# osi-brain_rev_1.net
KiCad netlist of a schematic drawn in EAGLE
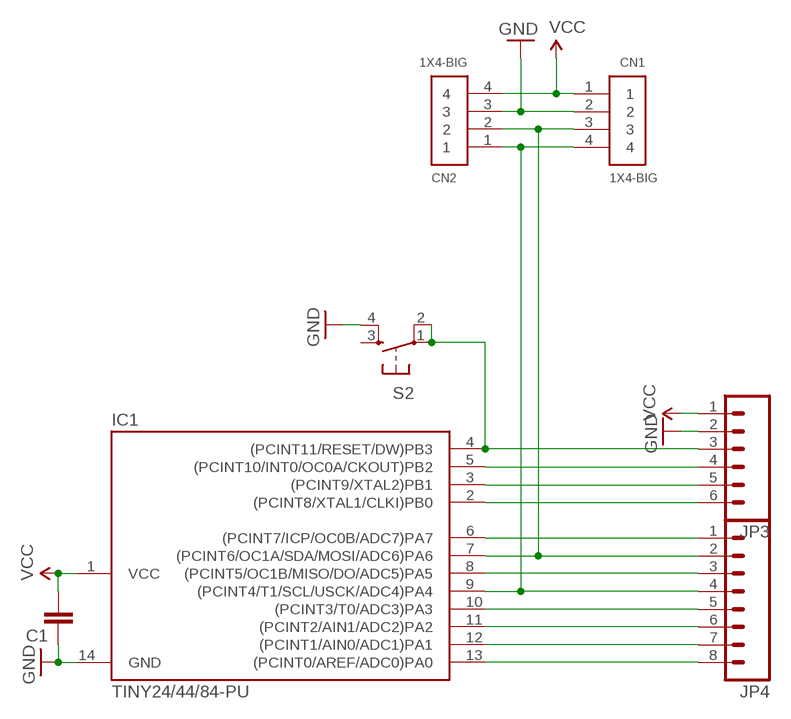
[diagram p0: schematic, sheet 1]

(export (version "E")
  (design (tool "Eeschema 10.0.6"))
  (components
    (comp (ref "C1")
      (value "CAPKIT")
      (footprint "eagle-import:CAP-PTH-SMALL-KIT")
      (libsource (lib "eagle-import") (part "CAPKIT"))
    )
    (comp (ref "CN1")
      (value "1X4-BIG")
      (footprint "eagle-import:1X04-BIG")
      (libsource (lib "eagle-import") (part "1X4-BIG"))
    )
    (comp (ref "CN2")
      (value "1X4-BIG")
      (footprint "eagle-import:1X04-BIG")
      (libsource (lib "eagle-import") (part "1X4-BIG"))
    )
    (comp (ref "IC1")
      (value "TINY24/44/84-PU")
      (footprint "eagle-import:DIL14")
      (libsource (lib "eagle-import") (part "TINY24/44/84-PU"))
    )
    (comp (ref "JP3")
      (value "M06SIP")
      (footprint "eagle-import:1X06")
      (libsource (lib "eagle-import") (part "M06SIP"))
    )
    (comp (ref "JP4")
      (value "M081X08")
      (footprint "eagle-import:1X08")
      (libsource (lib "eagle-import") (part "M081X08"))
    )
    (comp (ref "S2")
      (value "TAC_SWITCHPTH")
      (footprint "eagle-import:TACTILE-PTH")
      (libsource (lib "eagle-import") (part "TAC_SWITCHPTH"))
    )
  )
  (nets
    (net (code "1") (name "GND") (class "Default")
      (node (ref "C1") (pin "1") (pinfunction "1_1") (pintype "passive"))
      (node (ref "CN1") (pin "2") (pinfunction "2_2") (pintype "bidirectional"))
      (node (ref "CN2") (pin "3") (pinfunction "3_3") (pintype "bidirectional"))
      (node (ref "IC1") (pin "14") (pinfunction "GND_14") (pintype "power_in"))
      (node (ref "JP3") (pin "2") (pinfunction "2_2") (pintype "passive"))
      (node (ref "S2") (pin "4") (pinfunction "4_4") (pintype "passive"))
    )
    (net (code "2") (name "Net-(IC1-(PCINT0{slash}AREF{slash}ADC0)PA0)") (class "Default")
      (node (ref "IC1") (pin "13") (pinfunction "(PCINT0/AREF/ADC0)PA0_13") (pintype "bidirectional"))
      (node (ref "JP4") (pin "8") (pinfunction "8_8") (pintype "passive"))
    )
    (net (code "3") (name "Net-(IC1-(PCINT1{slash}AIN0{slash}ADC1)PA1)") (class "Default")
      (node (ref "IC1") (pin "12") (pinfunction "(PCINT1/AIN0/ADC1)PA1_12") (pintype "bidirectional"))
      (node (ref "JP4") (pin "7") (pinfunction "7_7") (pintype "passive"))
    )
    (net (code "4") (name "Net-(IC1-(PCINT2{slash}AIN1{slash}ADC2)PA2)") (class "Default")
      (node (ref "IC1") (pin "11") (pinfunction "(PCINT2/AIN1/ADC2)PA2_11") (pintype "bidirectional"))
      (node (ref "JP4") (pin "6") (pinfunction "6_6") (pintype "passive"))
    )
    (net (code "5") (name "Net-(IC1-(PCINT3{slash}T0{slash}ADC3)PA3)") (class "Default")
      (node (ref "IC1") (pin "10") (pinfunction "(PCINT3/T0/ADC3)PA3_10") (pintype "bidirectional"))
      (node (ref "JP4") (pin "5") (pinfunction "5_5") (pintype "passive"))
    )
    (net (code "6") (name "Net-(IC1-(PCINT4{slash}T1{slash}SCL{slash}USCK{slash}ADC4)PA4)") (class "Default")
      (node (ref "CN1") (pin "4") (pinfunction "4_4") (pintype "bidirectional"))
      (node (ref "CN2") (pin "1") (pinfunction "1_1") (pintype "bidirectional"))
      (node (ref "IC1") (pin "9") (pinfunction "(PCINT4/T1/SCL/USCK/ADC4)PA4_9") (pintype "bidirectional"))
      (node (ref "JP4") (pin "4") (pinfunction "4_4") (pintype "passive"))
    )
    (net (code "7") (name "Net-(IC1-(PCINT5{slash}OC1B{slash}MISO{slash}DO{slash}ADC5)PA5)") (class "Default")
      (node (ref "IC1") (pin "8") (pinfunction "(PCINT5/OC1B/MISO/DO/ADC5)PA5_8") (pintype "bidirectional"))
      (node (ref "JP4") (pin "3") (pinfunction "3_3") (pintype "passive"))
    )
    (net (code "8") (name "Net-(IC1-(PCINT6{slash}OC1A{slash}SDA{slash}MOSI{slash}ADC6)PA6)") (class "Default")
      (node (ref "CN1") (pin "3") (pinfunction "3_3") (pintype "bidirectional"))
      (node (ref "CN2") (pin "2") (pinfunction "2_2") (pintype "bidirectional"))
      (node (ref "IC1") (pin "7") (pinfunction "(PCINT6/OC1A/SDA/MOSI/ADC6)PA6_7") (pintype "bidirectional"))
      (node (ref "JP4") (pin "2") (pinfunction "2_2") (pintype "passive"))
    )
    (net (code "9") (name "Net-(IC1-(PCINT7{slash}ICP{slash}OC0B{slash}ADC7)PA7)") (class "Default")
      (node (ref "IC1") (pin "6") (pinfunction "(PCINT7/ICP/OC0B/ADC7)PA7_6") (pintype "bidirectional"))
      (node (ref "JP4") (pin "1") (pinfunction "1_1") (pintype "passive"))
    )
    (net (code "10") (name "Net-(IC1-(PCINT8{slash}XTAL1{slash}CLKI)PB0)") (class "Default")
      (node (ref "IC1") (pin "2") (pinfunction "(PCINT8/XTAL1/CLKI)PB0_2") (pintype "bidirectional"))
      (node (ref "JP3") (pin "6") (pinfunction "6_6") (pintype "passive"))
    )
    (net (code "11") (name "Net-(IC1-(PCINT9{slash}XTAL2)PB1)") (class "Default")
      (node (ref "IC1") (pin "3") (pinfunction "(PCINT9/XTAL2)PB1_3") (pintype "bidirectional"))
      (node (ref "JP3") (pin "5") (pinfunction "5_5") (pintype "passive"))
    )
    (net (code "12") (name "Net-(IC1-(PCINT10{slash}INT0{slash}OC0A{slash}CKOUT)PB2)") (class "Default")
      (node (ref "IC1") (pin "5") (pinfunction "(PCINT10/INT0/OC0A/CKOUT)PB2_5") (pintype "bidirectional"))
      (node (ref "JP3") (pin "4") (pinfunction "4_4") (pintype "passive"))
    )
    (net (code "13") (name "Net-(IC1-(PCINT11{slash}RESET{slash}DW)PB3)") (class "Default")
      (node (ref "IC1") (pin "4") (pinfunction "(PCINT11/RESET/DW)PB3_4") (pintype "bidirectional"))
      (node (ref "JP3") (pin "3") (pinfunction "3_3") (pintype "passive"))
      (node (ref "S2") (pin "1") (pinfunction "1_1") (pintype "passive"))
      (node (ref "S2") (pin "2") (pinfunction "2_2") (pintype "passive"))
    )
    (net (code "14") (name "VCC") (class "Default")
      (node (ref "C1") (pin "2") (pinfunction "2_2") (pintype "passive"))
      (node (ref "CN1") (pin "1") (pinfunction "1_1") (pintype "bidirectional"))
      (node (ref "CN2") (pin "4") (pinfunction "4_4") (pintype "bidirectional"))
      (node (ref "IC1") (pin "1") (pinfunction "VCC_1") (pintype "power_in"))
      (node (ref "JP3") (pin "1") (pinfunction "1_1") (pintype "passive"))
    )
    (net (code "15") (name "unconnected-(S2-Pad3)") (class "Default")
      (node (ref "S2") (pin "3") (pinfunction "3_3") (pintype "passive"))
    )
  )
)
